# GS_Connector.net
KiCad netlist of a schematic drawn in Altium Designer
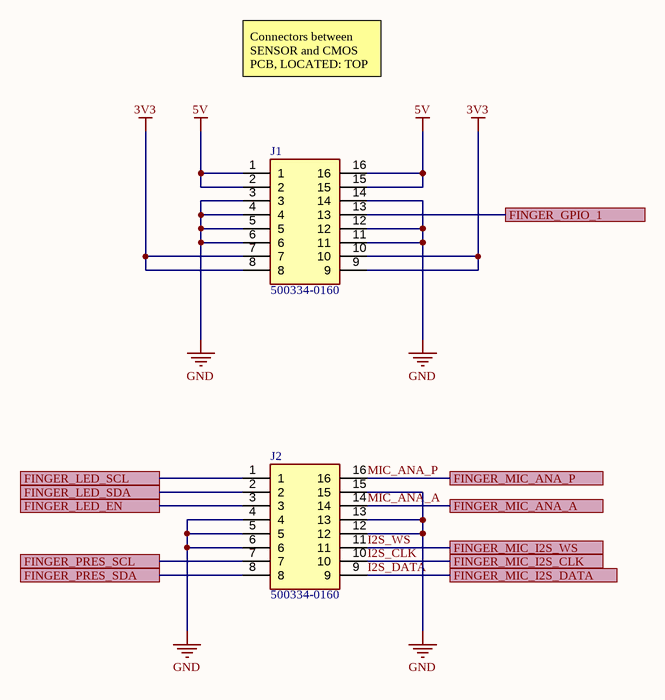
[diagram p0: GS_Connector.SchDoc]

(export (version "E")
  (design (tool "Eeschema 10.0.6"))
  (components
    (comp (ref "J1")
      (value "500334-0160")
      (footprint "SamacSys:5003340160")
      (description "Connector")
      (fields (field (name "MOUSER PART NUMBER") "538-500334-0160"))
      (libsource (lib "SamacSys") (part "500334-0160"))
    )
    (comp (ref "J2")
      (value "500334-0160")
      (footprint "SamacSys:5003340160")
      (description "Connector")
      (fields (field (name "MOUSER PART NUMBER") "538-500334-0160"))
      (libsource (lib "SamacSys") (part "500334-0160"))
    )
  )
  (nets
    (net (code "1") (name "/FINGER_GPIO_1") (class "Default")
      (node (ref "J1") (pin "13") (pinfunction "13_13") (pintype "passive"))
    )
    (net (code "2") (name "/FINGER_LED_EN") (class "Default")
      (node (ref "J2") (pin "3") (pinfunction "3_3") (pintype "passive"))
    )
    (net (code "3") (name "/FINGER_LED_SCL") (class "Default")
      (node (ref "J2") (pin "1") (pinfunction "1_1") (pintype "passive"))
    )
    (net (code "4") (name "/FINGER_LED_SDA") (class "Default")
      (node (ref "J2") (pin "2") (pinfunction "2_2") (pintype "passive"))
    )
    (net (code "5") (name "/FINGER_PRES_SCL") (class "Default")
      (node (ref "J2") (pin "7") (pinfunction "7_7") (pintype "passive"))
    )
    (net (code "6") (name "/FINGER_PRES_SDA") (class "Default")
      (node (ref "J2") (pin "8") (pinfunction "8_8") (pintype "passive"))
    )
    (net (code "7") (name "/I2S_CLK") (class "Default")
      (node (ref "J2") (pin "10") (pinfunction "10_10") (pintype "passive"))
    )
    (net (code "8") (name "/I2S_DATA") (class "Default")
      (node (ref "J2") (pin "9") (pinfunction "9_9") (pintype "passive"))
    )
    (net (code "9") (name "/I2S_WS") (class "Default")
      (node (ref "J2") (pin "11") (pinfunction "11_11") (pintype "passive"))
    )
    (net (code "10") (name "/MIC_ANA_A") (class "Default")
      (node (ref "J2") (pin "14") (pinfunction "14_14") (pintype "passive"))
    )
    (net (code "11") (name "/MIC_ANA_P") (class "Default")
      (node (ref "J2") (pin "16") (pinfunction "16_16") (pintype "passive"))
    )
    (net (code "12") (name "3V3") (class "Default")
      (node (ref "J1") (pin "10") (pinfunction "10_10") (pintype "passive"))
      (node (ref "J1") (pin "7") (pinfunction "7_7") (pintype "passive"))
      (node (ref "J1") (pin "8") (pinfunction "8_8") (pintype "passive"))
      (node (ref "J1") (pin "9") (pinfunction "9_9") (pintype "passive"))
    )
    (net (code "13") (name "5V") (class "Default")
      (node (ref "J1") (pin "1") (pinfunction "1_1") (pintype "passive"))
      (node (ref "J1") (pin "15") (pinfunction "15_15") (pintype "passive"))
      (node (ref "J1") (pin "16") (pinfunction "16_16") (pintype "passive"))
      (node (ref "J1") (pin "2") (pinfunction "2_2") (pintype "passive"))
    )
    (net (code "14") (name "GND") (class "Default")
      (node (ref "J1") (pin "11") (pinfunction "11_11") (pintype "passive"))
      (node (ref "J1") (pin "12") (pinfunction "12_12") (pintype "passive"))
      (node (ref "J1") (pin "14") (pinfunction "14_14") (pintype "passive"))
      (node (ref "J1") (pin "3") (pinfunction "3_3") (pintype "passive"))
      (node (ref "J1") (pin "4") (pinfunction "4_4") (pintype "passive"))
      (node (ref "J1") (pin "5") (pinfunction "5_5") (pintype "passive"))
      (node (ref "J1") (pin "6") (pinfunction "6_6") (pintype "passive"))
      (node (ref "J2") (pin "12") (pinfunction "12_12") (pintype "passive"))
      (node (ref "J2") (pin "13") (pinfunction "13_13") (pintype "passive"))
      (node (ref "J2") (pin "15") (pinfunction "15_15") (pintype "passive"))
      (node (ref "J2") (pin "4") (pinfunction "4_4") (pintype "passive"))
      (node (ref "J2") (pin "5") (pinfunction "5_5") (pintype "passive"))
      (node (ref "J2") (pin "6") (pinfunction "6_6") (pintype "passive"))
    )
  )
)
